# child.net
KiCad netlist of a schematic drawn in EAGLE
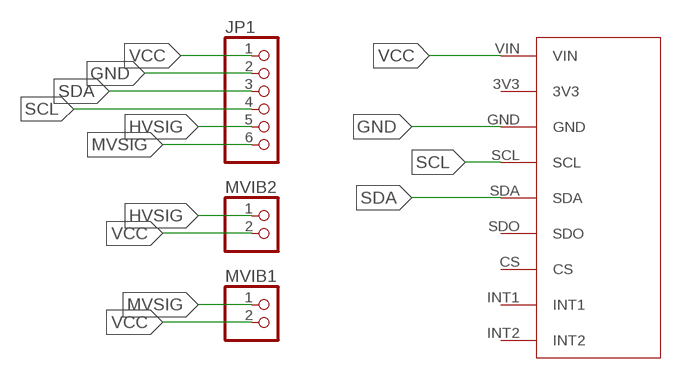
[diagram p0: schematic, sheet 1]

(export (version "E")
  (design (tool "Eeschema 10.0.6"))
  (components
    (comp (ref "ACCEL")
      (value "ADAFRUITADXL343")
      (footprint "eagle-import:ADAFRUITADXL343")
      (libsource (lib "eagle-import") (part "ADAFRUITADXL343"))
    )
    (comp (ref "JP1")
      (value "PINHD-1X6")
      (footprint "eagle-import:1X06")
      (libsource (lib "eagle-import") (part "PINHD-1X6"))
    )
    (comp (ref "MVIB1")
      (value "PINHD-1X2")
      (footprint "eagle-import:1X02")
      (libsource (lib "eagle-import") (part "PINHD-1X2"))
    )
    (comp (ref "MVIB2")
      (value "PINHD-1X2")
      (footprint "eagle-import:1X02")
      (libsource (lib "eagle-import") (part "PINHD-1X2"))
    )
  )
  (nets
    (net (code "1") (name "GND") (class "Default")
      (node (ref "ACCEL") (pin "GND") (pinfunction "GND_GND") (pintype "bidirectional"))
      (node (ref "JP1") (pin "2") (pinfunction "2_2") (pintype "passive"))
    )
    (net (code "2") (name "HVSIG") (class "Default")
      (node (ref "JP1") (pin "5") (pinfunction "5_5") (pintype "passive"))
      (node (ref "MVIB2") (pin "1") (pinfunction "1_1") (pintype "passive"))
    )
    (net (code "3") (name "MVSIG") (class "Default")
      (node (ref "JP1") (pin "6") (pinfunction "6_6") (pintype "passive"))
      (node (ref "MVIB1") (pin "1") (pinfunction "1_1") (pintype "passive"))
    )
    (net (code "4") (name "SCL") (class "Default")
      (node (ref "ACCEL") (pin "SCL") (pinfunction "SCL_SCL") (pintype "bidirectional"))
      (node (ref "JP1") (pin "4") (pinfunction "4_4") (pintype "passive"))
    )
    (net (code "5") (name "SDA") (class "Default")
      (node (ref "ACCEL") (pin "SDA") (pinfunction "SDA_SDA") (pintype "bidirectional"))
      (node (ref "JP1") (pin "3") (pinfunction "3_3") (pintype "passive"))
    )
    (net (code "6") (name "VCC") (class "Default")
      (node (ref "ACCEL") (pin "VIN") (pinfunction "VIN_VIN") (pintype "bidirectional"))
      (node (ref "JP1") (pin "1") (pinfunction "1_1") (pintype "passive"))
      (node (ref "MVIB1") (pin "2") (pinfunction "2_2") (pintype "passive"))
      (node (ref "MVIB2") (pin "2") (pinfunction "2_2") (pintype "passive"))
    )
    (net (code "7") (name "unconnected-(ACCEL-Pad3V3)") (class "Default")
      (node (ref "ACCEL") (pin "3V3") (pinfunction "3V3_3V3") (pintype "bidirectional"))
    )
    (net (code "8") (name "unconnected-(ACCEL-PadCS)") (class "Default")
      (node (ref "ACCEL") (pin "CS") (pinfunction "CS_CS") (pintype "bidirectional"))
    )
    (net (code "9") (name "unconnected-(ACCEL-PadINT1)") (class "Default")
      (node (ref "ACCEL") (pin "INT1") (pinfunction "INT1_INT1") (pintype "bidirectional"))
    )
    (net (code "10") (name "unconnected-(ACCEL-PadINT2)") (class "Default")
      (node (ref "ACCEL") (pin "INT2") (pinfunction "INT2_INT2") (pintype "bidirectional"))
    )
    (net (code "11") (name "unconnected-(ACCEL-PadSDO)") (class "Default")
      (node (ref "ACCEL") (pin "SDO") (pinfunction "SDO_SDO") (pintype "bidirectional"))
    )
  )
)
